# satshakit128.net
KiCad netlist of a schematic drawn in EAGLE
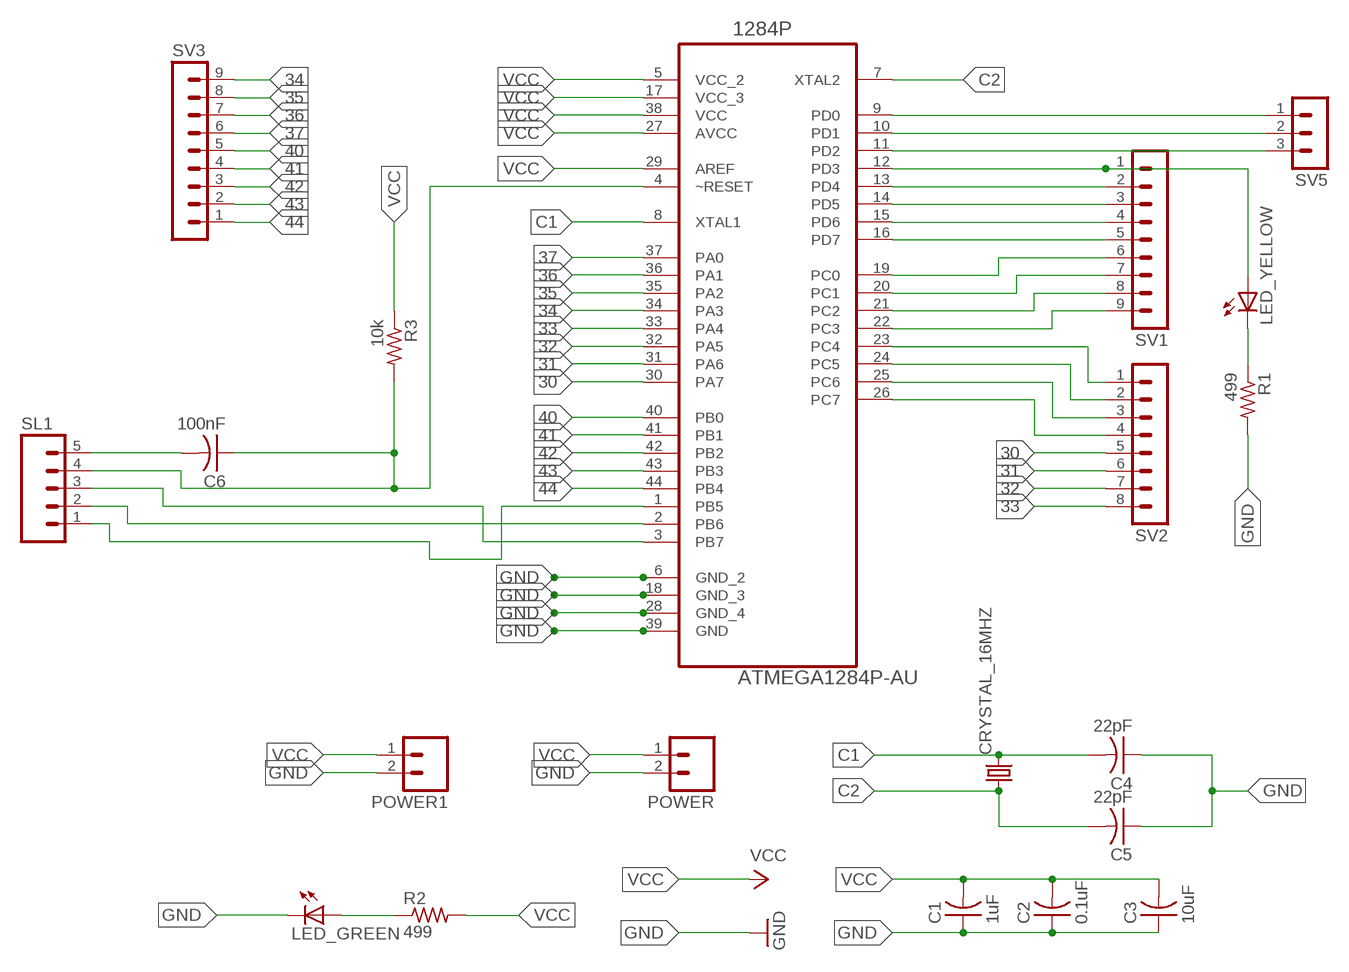
[diagram p0: schematic, sheet 1]

(export (version "E")
  (design (tool "Eeschema 10.0.6"))
  (components
    (comp (ref "1284P")
      (value "ATMEGA1284P-AU")
      (footprint "eagle-import:QFP80P1200X1200X120-44N")
      (libsource (lib "eagle-import") (part "ATMEGA1284P-AU"))
    )
    (comp (ref "C1")
      (value "1uF")
      (footprint "eagle-import:C1206")
      (libsource (lib "eagle-import") (part "CAP-US1206"))
    )
    (comp (ref "C2")
      (value "0.1uF")
      (footprint "eagle-import:C1206")
      (libsource (lib "eagle-import") (part "CAP-US1206"))
    )
    (comp (ref "C3")
      (value "10uF")
      (footprint "eagle-import:C1206")
      (libsource (lib "eagle-import") (part "CAP-US1206"))
    )
    (comp (ref "C4")
      (value "22pF")
      (footprint "eagle-import:C1206")
      (libsource (lib "eagle-import") (part "CAP-US1206"))
    )
    (comp (ref "C5")
      (value "22pF")
      (footprint "eagle-import:C1206")
      (libsource (lib "eagle-import") (part "CAP-US1206"))
    )
    (comp (ref "C6")
      (value "100nF")
      (footprint "eagle-import:C1206")
      (libsource (lib "eagle-import") (part "CAP-US1206"))
    )
    (comp (ref "CRYSTAL_16MHZ")
      (value "CRYSTALHC49UP")
      (footprint "eagle-import:HC49UP")
      (libsource (lib "eagle-import") (part "CRYSTALHC49UP"))
    )
    (comp (ref "LED_GREEN")
      (value "LED1206")
      (footprint "eagle-import:1206")
      (libsource (lib "eagle-import") (part "LED1206"))
    )
    (comp (ref "LED_YELLOW")
      (value "LED1206")
      (footprint "eagle-import:1206")
      (libsource (lib "eagle-import") (part "LED1206"))
    )
    (comp (ref "POWER")
      (value "M02")
      (footprint "eagle-import:02P")
      (libsource (lib "eagle-import") (part "M02"))
    )
    (comp (ref "POWER1")
      (value "M02")
      (footprint "eagle-import:02P")
      (libsource (lib "eagle-import") (part "M02"))
    )
    (comp (ref "R1")
      (value "499")
      (footprint "eagle-import:R1206")
      (libsource (lib "eagle-import") (part "RES-US1206"))
    )
    (comp (ref "R2")
      (value "499")
      (footprint "eagle-import:R1206")
      (libsource (lib "eagle-import") (part "RES-US1206"))
    )
    (comp (ref "R3")
      (value "10k")
      (footprint "eagle-import:R1206")
      (libsource (lib "eagle-import") (part "RES-US1206"))
    )
    (comp (ref "SL1")
      (value "M05")
      (footprint "eagle-import:05P")
      (libsource (lib "eagle-import") (part "M05"))
    )
    (comp (ref "SV1")
      (value "MA09-1")
      (footprint "eagle-import:MA09-1")
      (libsource (lib "eagle-import") (part "MA09-1"))
    )
    (comp (ref "SV2")
      (value "MA08-1")
      (footprint "eagle-import:MA08-1")
      (libsource (lib "eagle-import") (part "MA08-1"))
    )
    (comp (ref "SV3")
      (value "MA09-1")
      (footprint "eagle-import:MA09-1")
      (libsource (lib "eagle-import") (part "MA09-1"))
    )
    (comp (ref "SV5")
      (value "MA03-1")
      (footprint "eagle-import:MA03-1")
      (libsource (lib "eagle-import") (part "MA03-1"))
    )
  )
  (nets
    (net (code "1") (name "30") (class "Default")
      (node (ref "1284P") (pin "30") (pinfunction "PA7_30") (pintype "bidirectional"))
      (node (ref "SV2") (pin "5") (pinfunction "5_5") (pintype "passive"))
    )
    (net (code "2") (name "31") (class "Default")
      (node (ref "1284P") (pin "31") (pinfunction "PA6_31") (pintype "bidirectional"))
      (node (ref "SV2") (pin "6") (pinfunction "6_6") (pintype "passive"))
    )
    (net (code "3") (name "32") (class "Default")
      (node (ref "1284P") (pin "32") (pinfunction "PA5_32") (pintype "bidirectional"))
      (node (ref "SV2") (pin "7") (pinfunction "7_7") (pintype "passive"))
    )
    (net (code "4") (name "33") (class "Default")
      (node (ref "1284P") (pin "33") (pinfunction "PA4_33") (pintype "bidirectional"))
      (node (ref "SV2") (pin "8") (pinfunction "8_8") (pintype "passive"))
    )
    (net (code "5") (name "34") (class "Default")
      (node (ref "1284P") (pin "34") (pinfunction "PA3_34") (pintype "bidirectional"))
      (node (ref "SV3") (pin "9") (pinfunction "9_9") (pintype "passive"))
    )
    (net (code "6") (name "35") (class "Default")
      (node (ref "1284P") (pin "35") (pinfunction "PA2_35") (pintype "bidirectional"))
      (node (ref "SV3") (pin "8") (pinfunction "8_8") (pintype "passive"))
    )
    (net (code "7") (name "36") (class "Default")
      (node (ref "1284P") (pin "36") (pinfunction "PA1_36") (pintype "bidirectional"))
      (node (ref "SV3") (pin "7") (pinfunction "7_7") (pintype "passive"))
    )
    (net (code "8") (name "37") (class "Default")
      (node (ref "1284P") (pin "37") (pinfunction "PA0_37") (pintype "bidirectional"))
      (node (ref "SV3") (pin "6") (pinfunction "6_6") (pintype "passive"))
    )
    (net (code "9") (name "40") (class "Default")
      (node (ref "1284P") (pin "40") (pinfunction "PB0_40") (pintype "bidirectional"))
      (node (ref "SV3") (pin "5") (pinfunction "5_5") (pintype "passive"))
    )
    (net (code "10") (name "41") (class "Default")
      (node (ref "1284P") (pin "41") (pinfunction "PB1_41") (pintype "bidirectional"))
      (node (ref "SV3") (pin "4") (pinfunction "4_4") (pintype "passive"))
    )
    (net (code "11") (name "42") (class "Default")
      (node (ref "1284P") (pin "42") (pinfunction "PB2_42") (pintype "bidirectional"))
      (node (ref "SV3") (pin "3") (pinfunction "3_3") (pintype "passive"))
    )
    (net (code "12") (name "43") (class "Default")
      (node (ref "1284P") (pin "43") (pinfunction "PB3_43") (pintype "bidirectional"))
      (node (ref "SV3") (pin "2") (pinfunction "2_2") (pintype "passive"))
    )
    (net (code "13") (name "44") (class "Default")
      (node (ref "1284P") (pin "44") (pinfunction "PB4_44") (pintype "bidirectional"))
      (node (ref "SV3") (pin "1") (pinfunction "1_1") (pintype "passive"))
    )
    (net (code "14") (name "C1") (class "Default")
      (node (ref "1284P") (pin "8") (pinfunction "XTAL1_8") (pintype "input"))
      (node (ref "C4") (pin "2") (pinfunction "2_2") (pintype "passive"))
      (node (ref "CRYSTAL_16MHZ") (pin "2") (pinfunction "2_2") (pintype "passive"))
    )
    (net (code "15") (name "C2") (class "Default")
      (node (ref "1284P") (pin "7") (pinfunction "XTAL2_7") (pintype "output"))
      (node (ref "C5") (pin "2") (pinfunction "2_2") (pintype "passive"))
      (node (ref "CRYSTAL_16MHZ") (pin "1") (pinfunction "1_1") (pintype "passive"))
    )
    (net (code "16") (name "GND") (class "Default")
      (node (ref "1284P") (pin "6") (pinfunction "GND_2_6") (pintype "passive"))
      (node (ref "C1") (pin "1") (pinfunction "1_1") (pintype "passive"))
      (node (ref "C2") (pin "1") (pinfunction "1_1") (pintype "passive"))
      (node (ref "C3") (pin "1") (pinfunction "1_1") (pintype "passive"))
      (node (ref "C4") (pin "1") (pinfunction "1_1") (pintype "passive"))
      (node (ref "C5") (pin "1") (pinfunction "1_1") (pintype "passive"))
      (node (ref "LED_GREEN") (pin "2") (pinfunction "C_2") (pintype "passive"))
      (node (ref "POWER") (pin "2") (pinfunction "2_2") (pintype "passive"))
      (node (ref "POWER1") (pin "2") (pinfunction "2_2") (pintype "passive"))
      (node (ref "R1") (pin "2") (pinfunction "2_2") (pintype "passive"))
    )
    (net (code "17") (name "Net-(1284P-PB5)") (class "Default")
      (node (ref "1284P") (pin "1") (pinfunction "PB5_1") (pintype "bidirectional"))
      (node (ref "SL1") (pin "1") (pinfunction "1_1") (pintype "passive"))
    )
    (net (code "18") (name "Net-(1284P-PB6)") (class "Default")
      (node (ref "1284P") (pin "2") (pinfunction "PB6_2") (pintype "bidirectional"))
      (node (ref "SL1") (pin "2") (pinfunction "2_2") (pintype "passive"))
    )
    (net (code "19") (name "Net-(1284P-PB7)") (class "Default")
      (node (ref "1284P") (pin "3") (pinfunction "PB7_3") (pintype "bidirectional"))
      (node (ref "SL1") (pin "3") (pinfunction "3_3") (pintype "passive"))
    )
    (net (code "20") (name "Net-(1284P-PC0)") (class "Default")
      (node (ref "1284P") (pin "19") (pinfunction "PC0_19") (pintype "bidirectional"))
      (node (ref "SV1") (pin "6") (pinfunction "6_6") (pintype "passive"))
    )
    (net (code "21") (name "Net-(1284P-PC1)") (class "Default")
      (node (ref "1284P") (pin "20") (pinfunction "PC1_20") (pintype "bidirectional"))
      (node (ref "SV1") (pin "7") (pinfunction "7_7") (pintype "passive"))
    )
    (net (code "22") (name "Net-(1284P-PC2)") (class "Default")
      (node (ref "1284P") (pin "21") (pinfunction "PC2_21") (pintype "bidirectional"))
      (node (ref "SV1") (pin "8") (pinfunction "8_8") (pintype "passive"))
    )
    (net (code "23") (name "Net-(1284P-PC3)") (class "Default")
      (node (ref "1284P") (pin "22") (pinfunction "PC3_22") (pintype "bidirectional"))
      (node (ref "SV1") (pin "9") (pinfunction "9_9") (pintype "passive"))
    )
    (net (code "24") (name "Net-(1284P-PC4)") (class "Default")
      (node (ref "1284P") (pin "23") (pinfunction "PC4_23") (pintype "bidirectional"))
      (node (ref "SV2") (pin "1") (pinfunction "1_1") (pintype "passive"))
    )
    (net (code "25") (name "Net-(1284P-PC5)") (class "Default")
      (node (ref "1284P") (pin "24") (pinfunction "PC5_24") (pintype "bidirectional"))
      (node (ref "SV2") (pin "2") (pinfunction "2_2") (pintype "passive"))
    )
    (net (code "26") (name "Net-(1284P-PC6)") (class "Default")
      (node (ref "1284P") (pin "25") (pinfunction "PC6_25") (pintype "bidirectional"))
      (node (ref "SV2") (pin "3") (pinfunction "3_3") (pintype "passive"))
    )
    (net (code "27") (name "Net-(1284P-PC7)") (class "Default")
      (node (ref "1284P") (pin "26") (pinfunction "PC7_26") (pintype "bidirectional"))
      (node (ref "SV2") (pin "4") (pinfunction "4_4") (pintype "passive"))
    )
    (net (code "28") (name "Net-(1284P-PD0)") (class "Default")
      (node (ref "1284P") (pin "9") (pinfunction "PD0_9") (pintype "bidirectional"))
      (node (ref "SV5") (pin "1") (pinfunction "1_1") (pintype "passive"))
    )
    (net (code "29") (name "Net-(1284P-PD1)") (class "Default")
      (node (ref "1284P") (pin "10") (pinfunction "PD1_10") (pintype "bidirectional"))
      (node (ref "SV5") (pin "2") (pinfunction "2_2") (pintype "passive"))
    )
    (net (code "30") (name "Net-(1284P-PD2)") (class "Default")
      (node (ref "1284P") (pin "11") (pinfunction "PD2_11") (pintype "bidirectional"))
      (node (ref "SV5") (pin "3") (pinfunction "3_3") (pintype "passive"))
    )
    (net (code "31") (name "Net-(1284P-PD3)") (class "Default")
      (node (ref "1284P") (pin "12") (pinfunction "PD3_12") (pintype "bidirectional"))
      (node (ref "LED_YELLOW") (pin "1") (pinfunction "A_1") (pintype "passive"))
      (node (ref "SV1") (pin "1") (pinfunction "1_1") (pintype "passive"))
    )
    (net (code "32") (name "Net-(1284P-PD4)") (class "Default")
      (node (ref "1284P") (pin "13") (pinfunction "PD4_13") (pintype "bidirectional"))
      (node (ref "SV1") (pin "2") (pinfunction "2_2") (pintype "passive"))
    )
    (net (code "33") (name "Net-(1284P-PD5)") (class "Default")
      (node (ref "1284P") (pin "14") (pinfunction "PD5_14") (pintype "bidirectional"))
      (node (ref "SV1") (pin "3") (pinfunction "3_3") (pintype "passive"))
    )
    (net (code "34") (name "Net-(1284P-PD6)") (class "Default")
      (node (ref "1284P") (pin "15") (pinfunction "PD6_15") (pintype "bidirectional"))
      (node (ref "SV1") (pin "4") (pinfunction "4_4") (pintype "passive"))
    )
    (net (code "35") (name "Net-(1284P-PD7)") (class "Default")
      (node (ref "1284P") (pin "16") (pinfunction "PD7_16") (pintype "bidirectional"))
      (node (ref "SV1") (pin "5") (pinfunction "5_5") (pintype "passive"))
    )
    (net (code "36") (name "Net-(1284P-~{RESET})") (class "Default")
      (node (ref "1284P") (pin "4") (pinfunction "~{RESET}_4") (pintype "input"))
      (node (ref "C6") (pin "1") (pinfunction "1_1") (pintype "passive"))
      (node (ref "R3") (pin "2") (pinfunction "2_2") (pintype "passive"))
      (node (ref "SL1") (pin "4") (pinfunction "4_4") (pintype "passive"))
    )
    (net (code "37") (name "Net-(C6-Pad2)") (class "Default")
      (node (ref "C6") (pin "2") (pinfunction "2_2") (pintype "passive"))
      (node (ref "SL1") (pin "5") (pinfunction "5_5") (pintype "passive"))
    )
    (net (code "38") (name "Net-(LED_GREEN-A)") (class "Default")
      (node (ref "LED_GREEN") (pin "1") (pinfunction "A_1") (pintype "passive"))
      (node (ref "R2") (pin "1") (pinfunction "1_1") (pintype "passive"))
    )
    (net (code "39") (name "Net-(LED_YELLOW-C)") (class "Default")
      (node (ref "LED_YELLOW") (pin "2") (pinfunction "C_2") (pintype "passive"))
      (node (ref "R1") (pin "1") (pinfunction "1_1") (pintype "passive"))
    )
    (net (code "40") (name "VCC") (class "Default")
      (node (ref "1284P") (pin "17") (pinfunction "VCC_3_17") (pintype "power_in"))
      (node (ref "1284P") (pin "27") (pinfunction "AVCC_27") (pintype "power_in"))
      (node (ref "1284P") (pin "29") (pinfunction "AREF_29") (pintype "input"))
      (node (ref "1284P") (pin "5") (pinfunction "VCC_2_5") (pintype "power_in"))
      (node (ref "C1") (pin "2") (pinfunction "2_2") (pintype "passive"))
      (node (ref "C2") (pin "2") (pinfunction "2_2") (pintype "passive"))
      (node (ref "C3") (pin "2") (pinfunction "2_2") (pintype "passive"))
      (node (ref "POWER") (pin "1") (pinfunction "1_1") (pintype "passive"))
      (node (ref "POWER1") (pin "1") (pinfunction "1_1") (pintype "passive"))
      (node (ref "R2") (pin "2") (pinfunction "2_2") (pintype "passive"))
      (node (ref "R3") (pin "1") (pinfunction "1_1") (pintype "passive"))
    )
    (net (code "41") (name "unconnected-(1284P-GND-Pad39)") (class "Default")
      (node (ref "1284P") (pin "39") (pinfunction "GND_39") (pintype "passive"))
    )
    (net (code "42") (name "unconnected-(1284P-GND_3-Pad18)") (class "Default")
      (node (ref "1284P") (pin "18") (pinfunction "GND_3_18") (pintype "passive"))
    )
    (net (code "43") (name "unconnected-(1284P-GND_4-Pad28)") (class "Default")
      (node (ref "1284P") (pin "28") (pinfunction "GND_4_28") (pintype "passive"))
    )
    (net (code "44") (name "unconnected-(1284P-VCC-Pad38)") (class "Default")
      (node (ref "1284P") (pin "38") (pinfunction "VCC_38") (pintype "power_in"))
    )
  )
)
